# 12V_BuckConverter.net
KiCad netlist of a schematic drawn in Altium Designer
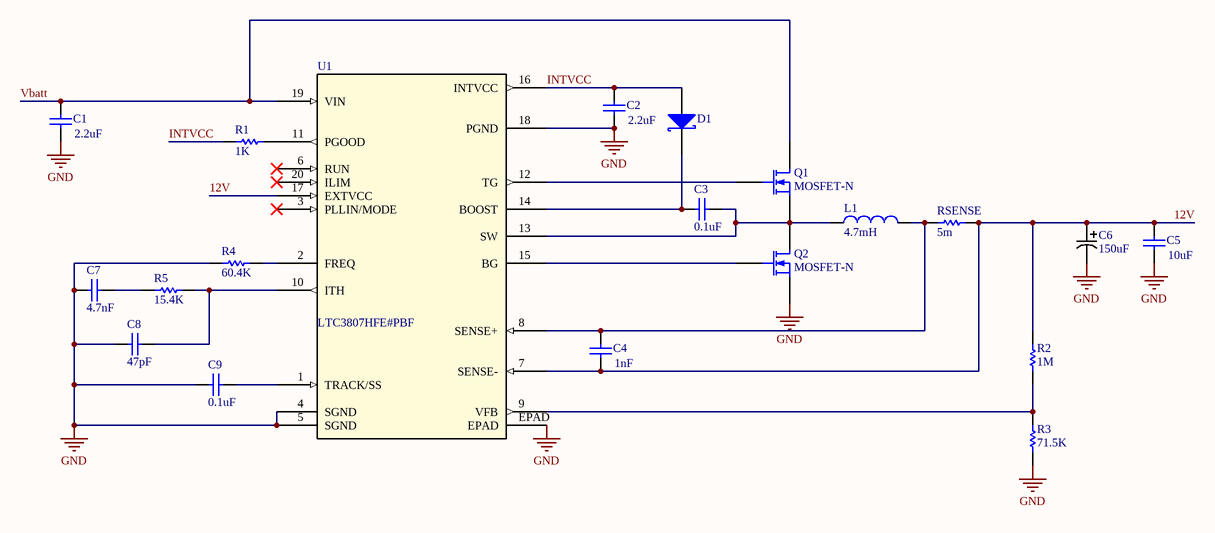
[diagram p0: 12V_BuckConverter.SchDoc]

(export (version "E")
  (design (tool "Eeschema 10.0.6"))
  (components
    (comp (ref "C1")
      (value "2.2uF")
      (footprint "1206")
      (description "Capacitor")
      (fields (field (name "Comment") "Cap") (field (name "PUBLISHER") "Altium Limited"))
      (libsource (lib "Miscellaneous Devices") (part "Cap"))
    )
    (comp (ref "C2")
      (value "2.2uF")
      (footprint "6-0805_N")
      (description "Capacitor")
      (fields (field (name "Comment") "Cap") (field (name "PUBLISHER") "Altium Limited"))
      (libsource (lib "Miscellaneous Devices") (part "Cap"))
    )
    (comp (ref "C3")
      (value "0.1uF")
      (footprint "6-0805_N")
      (description "Capacitor")
      (fields (field (name "Comment") "Cap") (field (name "PUBLISHER") "Altium Limited"))
      (libsource (lib "Miscellaneous Devices") (part "Cap"))
    )
    (comp (ref "C4")
      (value "1nF")
      (footprint "6-0805_N")
      (description "Capacitor")
      (fields (field (name "Comment") "Cap") (field (name "PUBLISHER") "Altium Limited"))
      (libsource (lib "Miscellaneous Devices") (part "Cap"))
    )
    (comp (ref "C5")
      (value "10uF")
      (footprint "1206")
      (description "Capacitor")
      (fields (field (name "Comment") "Cap") (field (name "PUBLISHER") "Altium Limited"))
      (libsource (lib "Miscellaneous Devices") (part "Cap"))
    )
    (comp (ref "C6")
      (value "150uF")
      (footprint "PCAP_SVP_F8")
      (description "No Description Available")
      (fields
        (field (name "MANUFACTURER_PART_NUMBER") "16SVP150M")
        (field (name "COPYRIGHT") "Copyright (C) 2018 Accelerated Designs. All rights reserved")
      )
      (libsource (lib "2020-02-11_03-36-15") (part "16SVP150M"))
    )
    (comp (ref "C7")
      (value "4.7nF")
      (footprint "6-0805_N")
      (description "Capacitor")
      (fields (field (name "Comment") "Cap") (field (name "PUBLISHER") "Altium Limited"))
      (libsource (lib "Miscellaneous Devices") (part "Cap"))
    )
    (comp (ref "C8")
      (value "47pF")
      (footprint "6-0805_N")
      (description "Capacitor")
      (fields (field (name "Comment") "Cap") (field (name "PUBLISHER") "Altium Limited"))
      (libsource (lib "Miscellaneous Devices") (part "Cap"))
    )
    (comp (ref "C9")
      (value "0.1uF")
      (footprint "6-0805_N")
      (description "Capacitor")
      (fields (field (name "Comment") "Cap") (field (name "PUBLISHER") "Altium Limited"))
      (libsource (lib "Miscellaneous Devices") (part "Cap"))
    )
    (comp (ref "D1")
      (value "D Schottky")
      (footprint "DFLS1100")
      (description "Schottky Diode")
      (fields (field (name "PUBLISHER") "Altium Limited"))
      (libsource (lib "Miscellaneous Devices") (part "D Schottky"))
    )
    (comp (ref "L1")
      (value "4.7mH")
      (footprint "WURTH 7443320470")
      (description "Inductor")
      (fields (field (name "PUBLISHER") "Altium Limited"))
      (libsource (lib "Miscellaneous Devices") (part "Inductor"))
    )
    (comp (ref "Q1")
      (value "MOSFET-N")
      (footprint "*SOT-669")
      (description "N-Channel MOSFET")
      (fields (field (name "PUBLISHER") "Altium Limited"))
      (libsource (lib "Miscellaneous Devices") (part "MOSFET-N"))
    )
    (comp (ref "Q2")
      (value "MOSFET-N")
      (footprint "*SOT-669")
      (description "N-Channel MOSFET")
      (fields (field (name "PUBLISHER") "Altium Limited"))
      (libsource (lib "Miscellaneous Devices") (part "MOSFET-N"))
    )
    (comp (ref "R1")
      (value "1K")
      (footprint "6-0805_N")
      (description "Resistor")
      (fields (field (name "Comment") "Res1") (field (name "PUBLISHER") "Altium Limited"))
      (libsource (lib "Miscellaneous Devices") (part "Res1"))
    )
    (comp (ref "R2")
      (value "1M")
      (footprint "6-0805_N")
      (description "Resistor")
      (fields (field (name "Comment") "Res1") (field (name "PUBLISHER") "Altium Limited"))
      (libsource (lib "Miscellaneous Devices") (part "Res1"))
    )
    (comp (ref "R3")
      (value "71.5K")
      (footprint "6-0805_N")
      (description "Resistor")
      (fields (field (name "Comment") "Res1") (field (name "PUBLISHER") "Altium Limited"))
      (libsource (lib "Miscellaneous Devices") (part "Res1"))
    )
    (comp (ref "R4")
      (value "60.4K")
      (footprint "6-0805_N")
      (description "Resistor")
      (fields (field (name "Comment") "Res1") (field (name "PUBLISHER") "Altium Limited"))
      (libsource (lib "Miscellaneous Devices") (part "Res1"))
    )
    (comp (ref "R5")
      (value "15.4K")
      (footprint "6-0805_N")
      (description "Resistor")
      (fields (field (name "Comment") "Res1") (field (name "PUBLISHER") "Altium Limited"))
      (libsource (lib "Miscellaneous Devices") (part "Res1"))
    )
    (comp (ref "RSENSE")
      (value "5m")
      (footprint "1206")
      (description "Resistor")
      (fields (field (name "Comment") "Res1") (field (name "PUBLISHER") "Altium Limited"))
      (libsource (lib "Miscellaneous Devices") (part "Res1"))
    )
    (comp (ref "U1")
      (value "LTC3807HFE#PBF")
      (footprint "TSSOP-20_FE/CB")
      (description "No Description Available")
      (fields (field (name "COPYRIGHT") "Copyright (C) 2018 Accelerated Designs. All rights reserved"))
      (libsource (lib "2020-02-10_00-18-24") (part "LTC3807HFE#PBF"))
    )
  )
  (nets
    (net (code "1") (name "/12V") (class "Default")
      (node (ref "C4") (pin "1") (pinfunction "1_1") (pintype "passive"))
      (node (ref "C5") (pin "2") (pinfunction "2_2") (pintype "passive"))
      (node (ref "C6") (pin "1") (pinfunction "1_1") (pintype "passive"))
      (node (ref "R2") (pin "1") (pinfunction "1_1") (pintype "passive"))
      (node (ref "RSENSE") (pin "1") (pinfunction "1_1") (pintype "passive"))
      (node (ref "U1") (pin "17") (pinfunction "EXTVCC_17") (pintype "input"))
      (node (ref "U1") (pin "7") (pinfunction "SENSE-_7") (pintype "input"))
    )
    (net (code "2") (name "/INTVCC") (class "Default")
      (node (ref "C2") (pin "2") (pinfunction "2_2") (pintype "passive"))
      (node (ref "D1") (pin "1") (pinfunction "A_1") (pintype "passive"))
      (node (ref "R1") (pin "2") (pinfunction "2_2") (pintype "passive"))
      (node (ref "U1") (pin "16") (pinfunction "INTVCC_16") (pintype "output"))
    )
    (net (code "3") (name "/Vbatt") (class "Default")
      (node (ref "C1") (pin "2") (pinfunction "2_2") (pintype "passive"))
      (node (ref "Q1") (pin "1") (pinfunction "D_1") (pintype "passive"))
      (node (ref "U1") (pin "19") (pinfunction "VIN_19") (pintype "input"))
    )
    (net (code "4") (name "GND") (class "Default")
      (node (ref "C1") (pin "1") (pinfunction "1_1") (pintype "passive"))
      (node (ref "C2") (pin "1") (pinfunction "1_1") (pintype "passive"))
      (node (ref "C5") (pin "1") (pinfunction "1_1") (pintype "passive"))
      (node (ref "C6") (pin "2") (pinfunction "2_2") (pintype "passive"))
      (node (ref "C7") (pin "2") (pinfunction "2_2") (pintype "passive"))
      (node (ref "C8") (pin "2") (pinfunction "2_2") (pintype "passive"))
      (node (ref "C9") (pin "2") (pinfunction "2_2") (pintype "passive"))
      (node (ref "Q2") (pin "3") (pinfunction "S_3") (pintype "passive"))
      (node (ref "R3") (pin "2") (pinfunction "2_2") (pintype "passive"))
      (node (ref "R4") (pin "2") (pinfunction "2_2") (pintype "passive"))
      (node (ref "U1") (pin "18") (pinfunction "PGND_18") (pintype "power_in"))
      (node (ref "U1") (pin "4") (pinfunction "SGND_4") (pintype "power_in"))
      (node (ref "U1") (pin "5") (pinfunction "SGND_5") (pintype "power_in"))
      (node (ref "U1") (pin "EPAD") (pinfunction "EPAD_EPAD") (pintype "passive"))
    )
    (net (code "5") (name "Net-(C7-Pad1)") (class "Default")
      (node (ref "C7") (pin "1") (pinfunction "1_1") (pintype "passive"))
      (node (ref "R5") (pin "2") (pinfunction "2_2") (pintype "passive"))
    )
    (net (code "6") (name "Net-(D1-K)") (class "Default")
      (node (ref "C3") (pin "2") (pinfunction "2_2") (pintype "passive"))
      (node (ref "D1") (pin "2") (pinfunction "K_2") (pintype "passive"))
      (node (ref "U1") (pin "14") (pinfunction "BOOST_14") (pintype "passive"))
    )
    (net (code "7") (name "Net-(Q1-G)") (class "Default")
      (node (ref "Q1") (pin "2") (pinfunction "G_2") (pintype "passive"))
      (node (ref "U1") (pin "12") (pinfunction "TG_12") (pintype "output"))
    )
    (net (code "8") (name "Net-(Q1-S)") (class "Default")
      (node (ref "C3") (pin "1") (pinfunction "1_1") (pintype "passive"))
      (node (ref "L1") (pin "1") (pinfunction "1_1") (pintype "passive"))
      (node (ref "Q1") (pin "3") (pinfunction "S_3") (pintype "passive"))
      (node (ref "Q2") (pin "1") (pinfunction "D_1") (pintype "passive"))
      (node (ref "U1") (pin "13") (pinfunction "SW_13") (pintype "passive"))
    )
    (net (code "9") (name "Net-(Q2-G)") (class "Default")
      (node (ref "Q2") (pin "2") (pinfunction "G_2") (pintype "passive"))
      (node (ref "U1") (pin "15") (pinfunction "BG_15") (pintype "passive"))
    )
    (net (code "10") (name "Net-(U1-FREQ)") (class "Default")
      (node (ref "R4") (pin "1") (pinfunction "1_1") (pintype "passive"))
      (node (ref "U1") (pin "2") (pinfunction "FREQ_2") (pintype "passive"))
    )
    (net (code "11") (name "Net-(U1-ITH)") (class "Default")
      (node (ref "C8") (pin "1") (pinfunction "1_1") (pintype "passive"))
      (node (ref "R5") (pin "1") (pinfunction "1_1") (pintype "passive"))
      (node (ref "U1") (pin "10") (pinfunction "ITH_10") (pintype "output"))
    )
    (net (code "12") (name "Net-(U1-PGOOD)") (class "Default")
      (node (ref "R1") (pin "1") (pinfunction "1_1") (pintype "passive"))
      (node (ref "U1") (pin "11") (pinfunction "PGOOD_11") (pintype "output"))
    )
    (net (code "13") (name "Net-(U1-SENSE+)") (class "Default")
      (node (ref "C4") (pin "2") (pinfunction "2_2") (pintype "passive"))
      (node (ref "L1") (pin "2") (pinfunction "2_2") (pintype "passive"))
      (node (ref "RSENSE") (pin "2") (pinfunction "2_2") (pintype "passive"))
      (node (ref "U1") (pin "8") (pinfunction "SENSE+_8") (pintype "input"))
    )
    (net (code "14") (name "Net-(U1-TRACK{slash}SS)") (class "Default")
      (node (ref "C9") (pin "1") (pinfunction "1_1") (pintype "passive"))
      (node (ref "U1") (pin "1") (pinfunction "TRACK/SS_1") (pintype "input"))
    )
    (net (code "15") (name "Net-(U1-VFB)") (class "Default")
      (node (ref "R2") (pin "2") (pinfunction "2_2") (pintype "passive"))
      (node (ref "R3") (pin "1") (pinfunction "1_1") (pintype "passive"))
      (node (ref "U1") (pin "9") (pinfunction "VFB_9") (pintype "output"))
    )
    (net (code "16") (name "unconnected-(U1-ILIM-Pad20)") (class "Default")
      (node (ref "U1") (pin "20") (pinfunction "ILIM_20") (pintype "input+no_connect"))
    )
    (net (code "17") (name "unconnected-(U1-PLLIN{slash}MODE-Pad3)") (class "Default")
      (node (ref "U1") (pin "3") (pinfunction "PLLIN/MODE_3") (pintype "input+no_connect"))
    )
    (net (code "18") (name "unconnected-(U1-RUN-Pad6)") (class "Default")
      (node (ref "U1") (pin "6") (pinfunction "RUN_6") (pintype "input+no_connect"))
    )
  )
)
